# ewod-1x4.net
KiCad netlist of a schematic drawn in EAGLE
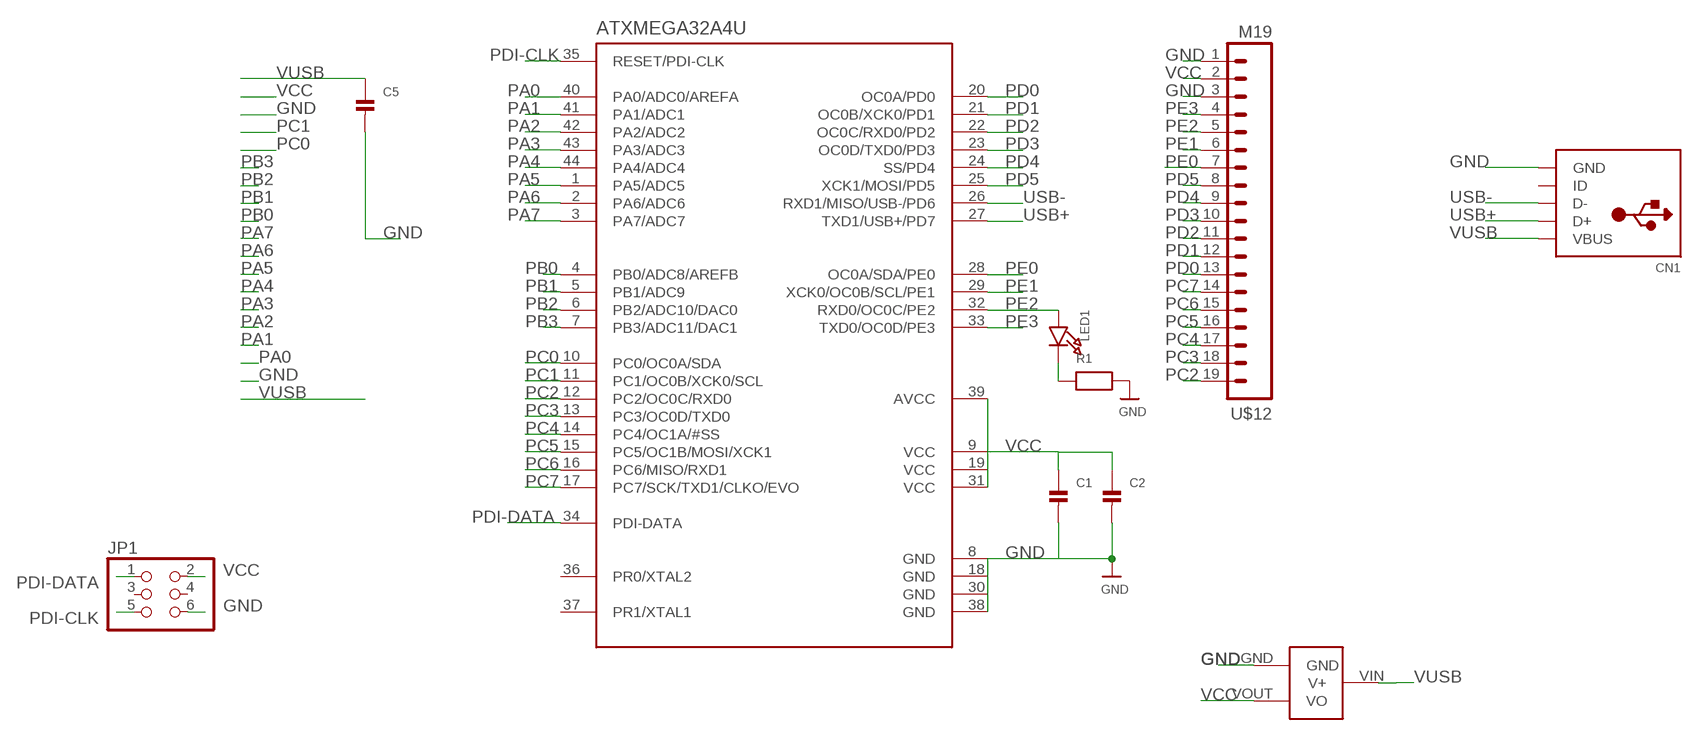
[diagram p0: schematic, sheet 1]
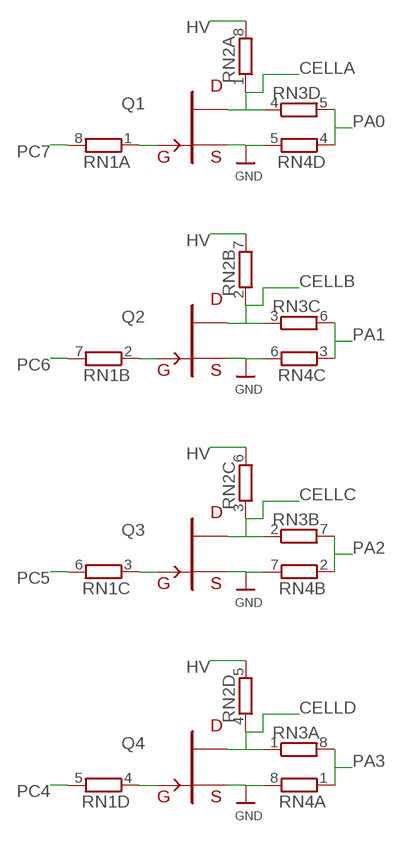
[diagram p1: schematic, sheet 2]
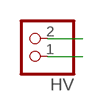
[diagram p2: schematic, sheet 3]

(export (version "E")
  (design (tool "Eeschema 10.0.6"))
  (components
    (comp (ref "HV")
      (value "HEADER-1X2ROUND")
      (footprint "eagle-import:1X02_ROUND")
      (libsource (lib "eagle-import") (part "HEADER-1X2ROUND"))
    )
    (comp (ref "Q1")
      (value "FET-N")
      (footprint "eagle-import:SOT23")
      (libsource (lib "eagle-import") (part "FET-N"))
    )
    (comp (ref "Q2")
      (value "FET-N")
      (footprint "eagle-import:SOT23")
      (libsource (lib "eagle-import") (part "FET-N"))
    )
    (comp (ref "Q3")
      (value "FET-N")
      (footprint "eagle-import:SOT23")
      (libsource (lib "eagle-import") (part "FET-N"))
    )
    (comp (ref "Q4")
      (value "FET-N")
      (footprint "eagle-import:SOT23")
      (libsource (lib "eagle-import") (part "FET-N"))
    )
    (comp (ref "RN1")
      (value "RNETWORK")
      (footprint "eagle-import:RN8P-4R-CRA06S")
      (libsource (lib "eagle-import") (part "RNETWORK"))
    )
    (comp (ref "RN2")
      (value "RNETWORK")
      (footprint "eagle-import:RN8P-4R-CRA06S")
      (libsource (lib "eagle-import") (part "RNETWORK"))
    )
    (comp (ref "RN3")
      (value "RNETWORK")
      (footprint "eagle-import:RN8P-4R-CRA06S")
      (libsource (lib "eagle-import") (part "RNETWORK"))
    )
    (comp (ref "RN4")
      (value "RNETWORK")
      (footprint "eagle-import:RN8P-4R-CRA06S")
      (libsource (lib "eagle-import") (part "RNETWORK"))
    )
    (comp (ref "ATXMEGA32A4U")
      (value "ATXMEGAXXA4U-AU")
      (footprint "eagle-import:TQFP-44")
      (libsource (lib "eagle-import") (part "ATXMEGAXXA4U-AU"))
    )
    (comp (ref "C1")
      (value "CAP_CERAMIC0603")
      (footprint "eagle-import:0603")
      (libsource (lib "eagle-import") (part "CAP_CERAMIC0603"))
    )
    (comp (ref "C2")
      (value "CAP_CERAMIC0603")
      (footprint "eagle-import:0603")
      (libsource (lib "eagle-import") (part "CAP_CERAMIC0603"))
    )
    (comp (ref "C5")
      (value "CAP_CERAMIC0603")
      (footprint "eagle-import:0603")
      (libsource (lib "eagle-import") (part "CAP_CERAMIC0603"))
    )
    (comp (ref "CN1")
      (value "USBMICROB")
      (footprint "eagle-import:USB-MICROB")
      (libsource (lib "eagle-import") (part "USBMICROB"))
    )
    (comp (ref "JP1")
      (value "HEADER-2X3")
      (footprint "eagle-import:2X03")
      (libsource (lib "eagle-import") (part "HEADER-2X3"))
    )
    (comp (ref "LED1")
      (value "LED0603")
      (footprint "eagle-import:CHIPLED_0603")
      (libsource (lib "eagle-import") (part "LED0603"))
    )
    (comp (ref "R1")
      (value "RESISTOR0603")
      (footprint "eagle-import:0603")
      (libsource (lib "eagle-import") (part "RESISTOR0603"))
    )
    (comp (ref "U$10")
      (value "MCP1700")
      (footprint "eagle-import:SOT23-3")
      (libsource (lib "eagle-import") (part "MCP1700"))
    )
    (comp (ref "U$12")
      (value "M19")
      (footprint "eagle-import:1X19")
      (libsource (lib "eagle-import") (part "M19"))
    )
  )
  (nets
    (net (code "1") (name "CELLA") (class "Default")
      (node (ref "Q1") (pin "3") (pinfunction "D_3") (pintype "bidirectional"))
      (node (ref "RN2") (pin "1") (pinfunction "1_1") (pintype "passive"))
      (node (ref "RN3") (pin "4") (pinfunction "1_4") (pintype "passive"))
    )
    (net (code "2") (name "CELLB") (class "Default")
      (node (ref "Q2") (pin "3") (pinfunction "D_3") (pintype "bidirectional"))
      (node (ref "RN2") (pin "2") (pinfunction "1_2") (pintype "passive"))
      (node (ref "RN3") (pin "3") (pinfunction "1_3") (pintype "passive"))
    )
    (net (code "3") (name "CELLC") (class "Default")
      (node (ref "Q3") (pin "3") (pinfunction "D_3") (pintype "bidirectional"))
      (node (ref "RN2") (pin "3") (pinfunction "1_3") (pintype "passive"))
      (node (ref "RN3") (pin "2") (pinfunction "1_2") (pintype "passive"))
    )
    (net (code "4") (name "CELLD") (class "Default")
      (node (ref "Q4") (pin "3") (pinfunction "D_3") (pintype "bidirectional"))
      (node (ref "RN2") (pin "4") (pinfunction "1_4") (pintype "passive"))
      (node (ref "RN3") (pin "1") (pinfunction "1_1") (pintype "passive"))
    )
    (net (code "5") (name "GND") (class "Default")
      (node (ref "ATXMEGA32A4U") (pin "18") (pinfunction "GND_18") (pintype "power_in"))
      (node (ref "ATXMEGA32A4U") (pin "30") (pinfunction "GND_30") (pintype "power_in"))
      (node (ref "ATXMEGA32A4U") (pin "38") (pinfunction "GND_38") (pintype "power_in"))
      (node (ref "ATXMEGA32A4U") (pin "8") (pinfunction "GND_8") (pintype "power_in"))
      (node (ref "C1") (pin "2") (pinfunction "P$2_2") (pintype "passive"))
      (node (ref "C2") (pin "2") (pinfunction "P$2_2") (pintype "passive"))
      (node (ref "C5") (pin "2") (pinfunction "P$2_2") (pintype "passive"))
      (node (ref "CN1") (pin "P5") (pinfunction "GND_P5") (pintype "power_in"))
      (node (ref "HV") (pin "2") (pinfunction "2_2") (pintype "passive"))
      (node (ref "JP1") (pin "6") (pinfunction "6_6") (pintype "passive"))
      (node (ref "Q1") (pin "2") (pinfunction "S_2") (pintype "bidirectional"))
      (node (ref "Q2") (pin "2") (pinfunction "S_2") (pintype "bidirectional"))
      (node (ref "Q3") (pin "2") (pinfunction "S_2") (pintype "bidirectional"))
      (node (ref "Q4") (pin "2") (pinfunction "S_2") (pintype "bidirectional"))
      (node (ref "R1") (pin "2") (pinfunction "2_2") (pintype "passive"))
      (node (ref "RN4") (pin "5") (pinfunction "2_5") (pintype "passive"))
      (node (ref "RN4") (pin "6") (pinfunction "2_6") (pintype "passive"))
      (node (ref "RN4") (pin "7") (pinfunction "2_7") (pintype "passive"))
      (node (ref "RN4") (pin "8") (pinfunction "2_8") (pintype "passive"))
      (node (ref "U$10") (pin "GND") (pinfunction "GND_GND") (pintype "bidirectional"))
      (node (ref "U$12") (pin "1") (pinfunction "1_1") (pintype "passive"))
      (node (ref "U$12") (pin "3") (pinfunction "3_3") (pintype "passive"))
    )
    (net (code "6") (name "HV") (class "Default")
      (node (ref "HV") (pin "1") (pinfunction "1_1") (pintype "passive"))
      (node (ref "RN2") (pin "5") (pinfunction "2_5") (pintype "passive"))
      (node (ref "RN2") (pin "6") (pinfunction "2_6") (pintype "passive"))
      (node (ref "RN2") (pin "7") (pinfunction "2_7") (pintype "passive"))
      (node (ref "RN2") (pin "8") (pinfunction "2_8") (pintype "passive"))
    )
    (net (code "7") (name "Net-(LED1-PadC)") (class "Default")
      (node (ref "LED1") (pin "C") (pinfunction "C_C") (pintype "passive"))
      (node (ref "R1") (pin "1") (pinfunction "1_1") (pintype "passive"))
    )
    (net (code "8") (name "Net-(Q1-G)") (class "Default")
      (node (ref "Q1") (pin "1") (pinfunction "G_1") (pintype "bidirectional"))
      (node (ref "RN1") (pin "1") (pinfunction "1_1") (pintype "passive"))
    )
    (net (code "9") (name "Net-(Q2-G)") (class "Default")
      (node (ref "Q2") (pin "1") (pinfunction "G_1") (pintype "bidirectional"))
      (node (ref "RN1") (pin "2") (pinfunction "1_2") (pintype "passive"))
    )
    (net (code "10") (name "Net-(Q3-G)") (class "Default")
      (node (ref "Q3") (pin "1") (pinfunction "G_1") (pintype "bidirectional"))
      (node (ref "RN1") (pin "3") (pinfunction "1_3") (pintype "passive"))
    )
    (net (code "11") (name "Net-(Q4-G)") (class "Default")
      (node (ref "Q4") (pin "1") (pinfunction "G_1") (pintype "bidirectional"))
      (node (ref "RN1") (pin "4") (pinfunction "1_4") (pintype "passive"))
    )
    (net (code "12") (name "PA0") (class "Default")
      (node (ref "ATXMEGA32A4U") (pin "40") (pinfunction "PA0/ADC0/AREFA_40") (pintype "bidirectional"))
      (node (ref "RN3") (pin "5") (pinfunction "2_5") (pintype "passive"))
      (node (ref "RN4") (pin "4") (pinfunction "1_4") (pintype "passive"))
    )
    (net (code "13") (name "PA1") (class "Default")
      (node (ref "ATXMEGA32A4U") (pin "41") (pinfunction "PA1/ADC1_41") (pintype "bidirectional"))
      (node (ref "RN3") (pin "6") (pinfunction "2_6") (pintype "passive"))
      (node (ref "RN4") (pin "3") (pinfunction "1_3") (pintype "passive"))
    )
    (net (code "14") (name "PA2") (class "Default")
      (node (ref "ATXMEGA32A4U") (pin "42") (pinfunction "PA2/ADC2_42") (pintype "bidirectional"))
      (node (ref "RN3") (pin "7") (pinfunction "2_7") (pintype "passive"))
      (node (ref "RN4") (pin "2") (pinfunction "1_2") (pintype "passive"))
    )
    (net (code "15") (name "PA3") (class "Default")
      (node (ref "ATXMEGA32A4U") (pin "43") (pinfunction "PA3/ADC3_43") (pintype "bidirectional"))
      (node (ref "RN3") (pin "8") (pinfunction "2_8") (pintype "passive"))
      (node (ref "RN4") (pin "1") (pinfunction "1_1") (pintype "passive"))
    )
    (net (code "16") (name "PA4") (class "Default")
      (node (ref "ATXMEGA32A4U") (pin "44") (pinfunction "PA4/ADC4_44") (pintype "bidirectional"))
    )
    (net (code "17") (name "PA5") (class "Default")
      (node (ref "ATXMEGA32A4U") (pin "1") (pinfunction "PA5/ADC5_1") (pintype "bidirectional"))
    )
    (net (code "18") (name "PA6") (class "Default")
      (node (ref "ATXMEGA32A4U") (pin "2") (pinfunction "PA6/ADC6_2") (pintype "bidirectional"))
    )
    (net (code "19") (name "PA7") (class "Default")
      (node (ref "ATXMEGA32A4U") (pin "3") (pinfunction "PA7/ADC7_3") (pintype "bidirectional"))
    )
    (net (code "20") (name "PB0") (class "Default")
      (node (ref "ATXMEGA32A4U") (pin "4") (pinfunction "PB0/ADC8/AREFB_4") (pintype "bidirectional"))
    )
    (net (code "21") (name "PB1") (class "Default")
      (node (ref "ATXMEGA32A4U") (pin "5") (pinfunction "PB1/ADC9_5") (pintype "bidirectional"))
    )
    (net (code "22") (name "PB2") (class "Default")
      (node (ref "ATXMEGA32A4U") (pin "6") (pinfunction "PB2/ADC10/DAC0_6") (pintype "bidirectional"))
    )
    (net (code "23") (name "PB3") (class "Default")
      (node (ref "ATXMEGA32A4U") (pin "7") (pinfunction "PB3/ADC11/DAC1_7") (pintype "bidirectional"))
    )
    (net (code "24") (name "PC0") (class "Default")
      (node (ref "ATXMEGA32A4U") (pin "10") (pinfunction "PC0/OC0A/SDA_10") (pintype "bidirectional"))
    )
    (net (code "25") (name "PC1") (class "Default")
      (node (ref "ATXMEGA32A4U") (pin "11") (pinfunction "PC1/OC0B/XCK0/SCL_11") (pintype "bidirectional"))
    )
    (net (code "26") (name "PC2") (class "Default")
      (node (ref "ATXMEGA32A4U") (pin "12") (pinfunction "PC2/OC0C/RXD0_12") (pintype "bidirectional"))
      (node (ref "U$12") (pin "19") (pinfunction "19_19") (pintype "passive"))
    )
    (net (code "27") (name "PC3") (class "Default")
      (node (ref "ATXMEGA32A4U") (pin "13") (pinfunction "PC3/OC0D/TXD0_13") (pintype "bidirectional"))
      (node (ref "U$12") (pin "18") (pinfunction "18_18") (pintype "passive"))
    )
    (net (code "28") (name "PC4") (class "Default")
      (node (ref "ATXMEGA32A4U") (pin "14") (pinfunction "PC4/OC1A/#SS_14") (pintype "bidirectional"))
      (node (ref "RN1") (pin "5") (pinfunction "2_5") (pintype "passive"))
      (node (ref "U$12") (pin "17") (pinfunction "17_17") (pintype "passive"))
    )
    (net (code "29") (name "PC5") (class "Default")
      (node (ref "ATXMEGA32A4U") (pin "15") (pinfunction "PC5/OC1B/MOSI/XCK1_15") (pintype "bidirectional"))
      (node (ref "RN1") (pin "6") (pinfunction "2_6") (pintype "passive"))
      (node (ref "U$12") (pin "16") (pinfunction "16_16") (pintype "passive"))
    )
    (net (code "30") (name "PC6") (class "Default")
      (node (ref "ATXMEGA32A4U") (pin "16") (pinfunction "PC6/MISO/RXD1_16") (pintype "bidirectional"))
      (node (ref "RN1") (pin "7") (pinfunction "2_7") (pintype "passive"))
      (node (ref "U$12") (pin "15") (pinfunction "15_15") (pintype "passive"))
    )
    (net (code "31") (name "PC7") (class "Default")
      (node (ref "ATXMEGA32A4U") (pin "17") (pinfunction "PC7/SCK/TXD1/CLKO/EVO_17") (pintype "bidirectional"))
      (node (ref "RN1") (pin "8") (pinfunction "2_8") (pintype "passive"))
      (node (ref "U$12") (pin "14") (pinfunction "14_14") (pintype "passive"))
    )
    (net (code "32") (name "PD0") (class "Default")
      (node (ref "ATXMEGA32A4U") (pin "20") (pinfunction "OC0A/PD0_20") (pintype "bidirectional"))
      (node (ref "U$12") (pin "13") (pinfunction "13_13") (pintype "passive"))
    )
    (net (code "33") (name "PD1") (class "Default")
      (node (ref "ATXMEGA32A4U") (pin "21") (pinfunction "OC0B/XCK0/PD1_21") (pintype "bidirectional"))
      (node (ref "U$12") (pin "12") (pinfunction "12_12") (pintype "passive"))
    )
    (net (code "34") (name "PD2") (class "Default")
      (node (ref "ATXMEGA32A4U") (pin "22") (pinfunction "OC0C/RXD0/PD2_22") (pintype "bidirectional"))
      (node (ref "U$12") (pin "11") (pinfunction "11_11") (pintype "passive"))
    )
    (net (code "35") (name "PD3") (class "Default")
      (node (ref "ATXMEGA32A4U") (pin "23") (pinfunction "OC0D/TXD0/PD3_23") (pintype "bidirectional"))
      (node (ref "U$12") (pin "10") (pinfunction "10_10") (pintype "passive"))
    )
    (net (code "36") (name "PD4") (class "Default")
      (node (ref "ATXMEGA32A4U") (pin "24") (pinfunction "SS/PD4_24") (pintype "bidirectional"))
      (node (ref "U$12") (pin "9") (pinfunction "9_9") (pintype "passive"))
    )
    (net (code "37") (name "PD5") (class "Default")
      (node (ref "ATXMEGA32A4U") (pin "25") (pinfunction "XCK1/MOSI/PD5_25") (pintype "bidirectional"))
      (node (ref "U$12") (pin "8") (pinfunction "8_8") (pintype "passive"))
    )
    (net (code "38") (name "PDI-CLK") (class "Default")
      (node (ref "ATXMEGA32A4U") (pin "35") (pinfunction "RESET/PDI-CLK_35") (pintype "input"))
      (node (ref "JP1") (pin "5") (pinfunction "5_5") (pintype "passive"))
    )
    (net (code "39") (name "PDI-DATA") (class "Default")
      (node (ref "ATXMEGA32A4U") (pin "34") (pinfunction "PDI-DATA_34") (pintype "bidirectional"))
      (node (ref "JP1") (pin "1") (pinfunction "1_1") (pintype "passive"))
    )
    (net (code "40") (name "PE0") (class "Default")
      (node (ref "ATXMEGA32A4U") (pin "28") (pinfunction "OC0A/SDA/PE0_28") (pintype "bidirectional"))
      (node (ref "U$12") (pin "7") (pinfunction "7_7") (pintype "passive"))
    )
    (net (code "41") (name "PE1") (class "Default")
      (node (ref "ATXMEGA32A4U") (pin "29") (pinfunction "XCK0/OC0B/SCL/PE1_29") (pintype "bidirectional"))
      (node (ref "U$12") (pin "6") (pinfunction "6_6") (pintype "passive"))
    )
    (net (code "42") (name "PE2") (class "Default")
      (node (ref "ATXMEGA32A4U") (pin "32") (pinfunction "RXD0/OC0C/PE2_32") (pintype "bidirectional"))
      (node (ref "LED1") (pin "A") (pinfunction "A_A") (pintype "passive"))
      (node (ref "U$12") (pin "5") (pinfunction "5_5") (pintype "passive"))
    )
    (net (code "43") (name "PE3") (class "Default")
      (node (ref "ATXMEGA32A4U") (pin "33") (pinfunction "TXD0/OC0D/PE3_33") (pintype "bidirectional"))
      (node (ref "U$12") (pin "4") (pinfunction "4_4") (pintype "passive"))
    )
    (net (code "44") (name "USB+") (class "Default")
      (node (ref "ATXMEGA32A4U") (pin "27") (pinfunction "TXD1/USB+/PD7_27") (pintype "bidirectional"))
      (node (ref "CN1") (pin "P3") (pinfunction "D+_P3") (pintype "bidirectional"))
    )
    (net (code "45") (name "USB-") (class "Default")
      (node (ref "ATXMEGA32A4U") (pin "26") (pinfunction "RXD1/MISO/USB-/PD6_26") (pintype "bidirectional"))
      (node (ref "CN1") (pin "P2") (pinfunction "D-_P2") (pintype "bidirectional"))
    )
    (net (code "46") (name "VCC") (class "Default")
      (node (ref "ATXMEGA32A4U") (pin "19") (pinfunction "VCC_19") (pintype "power_in"))
      (node (ref "ATXMEGA32A4U") (pin "31") (pinfunction "VCC_31") (pintype "power_in"))
      (node (ref "ATXMEGA32A4U") (pin "39") (pinfunction "AVCC_39") (pintype "power_in"))
      (node (ref "ATXMEGA32A4U") (pin "9") (pinfunction "VCC_9") (pintype "power_in"))
      (node (ref "C1") (pin "1") (pinfunction "P$1_1") (pintype "passive"))
      (node (ref "C2") (pin "1") (pinfunction "P$1_1") (pintype "passive"))
      (node (ref "JP1") (pin "2") (pinfunction "2_2") (pintype "passive"))
      (node (ref "U$10") (pin "VOUT") (pinfunction "VO_VOUT") (pintype "bidirectional"))
      (node (ref "U$12") (pin "2") (pinfunction "2_2") (pintype "passive"))
    )
    (net (code "47") (name "VUSB") (class "Default")
      (node (ref "C5") (pin "1") (pinfunction "P$1_1") (pintype "passive"))
      (node (ref "CN1") (pin "P1") (pinfunction "VBUS_P1") (pintype "power_in"))
      (node (ref "U$10") (pin "VIN") (pinfunction "V+_VIN") (pintype "bidirectional"))
    )
    (net (code "48") (name "unconnected-(ATXMEGA32A4U-PR0{slash}XTAL2-Pad36)") (class "Default")
      (node (ref "ATXMEGA32A4U") (pin "36") (pinfunction "PR0/XTAL2_36") (pintype "bidirectional"))
    )
    (net (code "49") (name "unconnected-(ATXMEGA32A4U-PR1{slash}XTAL1-Pad37)") (class "Default")
      (node (ref "ATXMEGA32A4U") (pin "37") (pinfunction "PR1/XTAL1_37") (pintype "bidirectional"))
    )
    (net (code "50") (name "unconnected-(CN1-ID-PadP4)") (class "Default")
      (node (ref "CN1") (pin "P4") (pinfunction "ID_P4") (pintype "bidirectional"))
    )
    (net (code "51") (name "unconnected-(JP1-Pad3)") (class "Default")
      (node (ref "JP1") (pin "3") (pinfunction "3_3") (pintype "passive"))
    )
    (net (code "52") (name "unconnected-(JP1-Pad4)") (class "Default")
      (node (ref "JP1") (pin "4") (pinfunction "4_4") (pintype "passive"))
    )
  )
)
